# MGC3130.net
KiCad netlist of a schematic drawn in Altium Designer
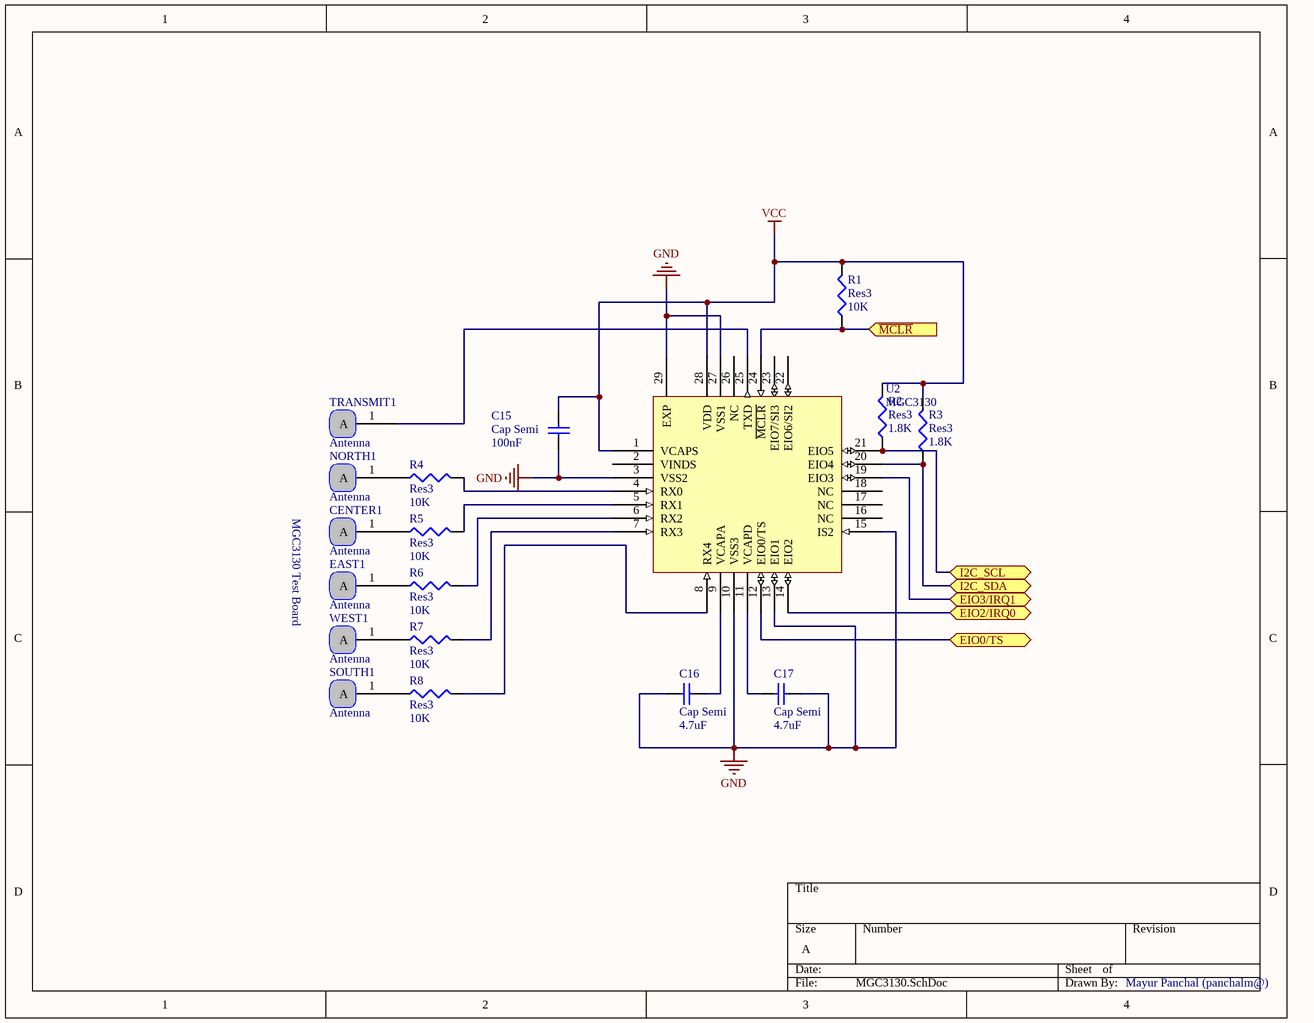
[diagram p0: MGC3130.SchDoc]

(export (version "E")
  (design (tool "Eeschema 10.0.6"))
  (components
    (comp (ref "C15")
      (value "Cap Semi")
      (footprint "1608[0603]")
      (description "Capacitor (Semiconductor SIM Model)")
      (fields (field (name "ALTIUM_VALUE") "100nF") (field (name "PUBLISHER") "Altium Limited"))
      (libsource (lib "Miscellaneous Devices") (part "Cap Semi"))
    )
    (comp (ref "C16")
      (value "Cap Semi")
      (footprint "1608[0603]")
      (description "Capacitor (Semiconductor SIM Model)")
      (fields (field (name "ALTIUM_VALUE") "4.7uF") (field (name "PUBLISHER") "Altium Limited"))
      (libsource (lib "Miscellaneous Devices") (part "Cap Semi"))
    )
    (comp (ref "C17")
      (value "Cap Semi")
      (footprint "1608[0603]")
      (description "Capacitor (Semiconductor SIM Model)")
      (fields (field (name "ALTIUM_VALUE") "4.7uF") (field (name "PUBLISHER") "Altium Limited"))
      (libsource (lib "Miscellaneous Devices") (part "Cap Semi"))
    )
    (comp (ref "CENTER1") (value "Antenna") (libsource (lib "Custom Parts") (part "Center Antenna")))
    (comp (ref "EAST1")
      (value "Antenna")
      (footprint "Vertical Electrode")
      (libsource (lib "Custom Parts") (part "East Antenna"))
    )
    (comp (ref "NORTH1")
      (value "Antenna")
      (footprint "Horizontal Electrode")
      (libsource (lib "Custom Parts") (part "North Antenna"))
    )
    (comp (ref "R1")
      (value "Res3")
      (footprint "J1-0603")
      (description "Resistor")
      (fields (field (name "ALTIUM_VALUE") "10K") (field (name "PUBLISHER") "Altium Limited"))
      (libsource (lib "Miscellaneous Devices") (part "Res3"))
    )
    (comp (ref "R2")
      (value "Res3")
      (footprint "J1-0603")
      (description "Resistor")
      (fields (field (name "ALTIUM_VALUE") "1.8K") (field (name "PUBLISHER") "Altium Limited"))
      (libsource (lib "Miscellaneous Devices") (part "Res3"))
    )
    (comp (ref "R3")
      (value "Res3")
      (footprint "J1-0603")
      (description "Resistor")
      (fields (field (name "ALTIUM_VALUE") "1.8K") (field (name "PUBLISHER") "Altium Limited"))
      (libsource (lib "Miscellaneous Devices") (part "Res3"))
    )
    (comp (ref "R4")
      (value "Res3")
      (footprint "J1-0603")
      (description "Resistor")
      (fields (field (name "ALTIUM_VALUE") "10K") (field (name "PUBLISHER") "Altium Limited"))
      (libsource (lib "Miscellaneous Devices") (part "Res3"))
    )
    (comp (ref "R5")
      (value "Res3")
      (footprint "J1-0603")
      (description "Resistor")
      (fields (field (name "ALTIUM_VALUE") "10K") (field (name "PUBLISHER") "Altium Limited"))
      (libsource (lib "Miscellaneous Devices") (part "Res3"))
    )
    (comp (ref "R6")
      (value "Res3")
      (footprint "J1-0603")
      (description "Resistor")
      (fields (field (name "ALTIUM_VALUE") "10K") (field (name "PUBLISHER") "Altium Limited"))
      (libsource (lib "Miscellaneous Devices") (part "Res3"))
    )
    (comp (ref "R7")
      (value "Res3")
      (footprint "J1-0603")
      (description "Resistor")
      (fields (field (name "ALTIUM_VALUE") "10K") (field (name "PUBLISHER") "Altium Limited"))
      (libsource (lib "Miscellaneous Devices") (part "Res3"))
    )
    (comp (ref "R8")
      (value "Res3")
      (footprint "J1-0603")
      (description "Resistor")
      (fields (field (name "ALTIUM_VALUE") "10K") (field (name "PUBLISHER") "Altium Limited"))
      (libsource (lib "Miscellaneous Devices") (part "Res3"))
    )
    (comp (ref "SOUTH1")
      (value "Antenna")
      (footprint "Horizontal Electrode")
      (libsource (lib "Custom Parts") (part "South Antenna"))
    )
    (comp (ref "TRANSMIT1") (value "Antenna") (libsource (lib "Custom Parts") (part "Transmit Antenna")))
    (comp (ref "U2")
      (value "MGC3130")
      (footprint "QFN28")
      (description "Gesture Recognition IC")
      (libsource (lib "Custom Parts") (part "MGC3130"))
    )
    (comp (ref "WEST1")
      (value "Antenna")
      (footprint "Vertical Electrode")
      (libsource (lib "Custom Parts") (part "West Antenna"))
    )
  )
  (nets
    (net (code "1") (name "/EIO0{slash}TS") (class "Default")
      (node (ref "U2") (pin "12") (pinfunction "EIO0/TS_12") (pintype "bidirectional"))
    )
    (net (code "2") (name "/EIO2{slash}IRQ0") (class "Default")
      (node (ref "U2") (pin "14") (pinfunction "EIO2_14") (pintype "bidirectional"))
    )
    (net (code "3") (name "/EIO3{slash}IRQ1") (class "Default")
      (node (ref "U2") (pin "19") (pinfunction "EIO3_19") (pintype "bidirectional"))
    )
    (net (code "4") (name "/I2C_SCL") (class "Default")
      (node (ref "R2") (pin "1") (pinfunction "1_1") (pintype "passive"))
      (node (ref "U2") (pin "21") (pinfunction "EIO5_21") (pintype "bidirectional"))
    )
    (net (code "5") (name "/I2C_SDA") (class "Default")
      (node (ref "R3") (pin "1") (pinfunction "1_1") (pintype "passive"))
      (node (ref "U2") (pin "20") (pinfunction "EIO4_20") (pintype "bidirectional"))
    )
    (net (code "6") (name "/~{MCLR}") (class "Default")
      (node (ref "R1") (pin "1") (pinfunction "1_1") (pintype "passive"))
      (node (ref "U2") (pin "24") (pinfunction "~{MCLR}_24") (pintype "input"))
    )
    (net (code "7") (name "GND") (class "Default")
      (node (ref "C15") (pin "1") (pinfunction "1_1") (pintype "passive"))
      (node (ref "C16") (pin "1") (pinfunction "1_1") (pintype "passive"))
      (node (ref "C17") (pin "2") (pinfunction "2_2") (pintype "passive"))
      (node (ref "U2") (pin "10") (pinfunction "VSS3_10") (pintype "power_in"))
      (node (ref "U2") (pin "13") (pinfunction "EIO1_13") (pintype "bidirectional"))
      (node (ref "U2") (pin "15") (pinfunction "IS2_15") (pintype "input"))
      (node (ref "U2") (pin "27") (pinfunction "VSS1_27") (pintype "power_in"))
      (node (ref "U2") (pin "29") (pinfunction "EXP_29") (pintype "power_in"))
      (node (ref "U2") (pin "3") (pinfunction "VSS2_3") (pintype "power_in"))
    )
    (net (code "8") (name "Net-(CENTER1-A)") (class "Default")
      (node (ref "CENTER1") (pin "1") (pinfunction "A_1") (pintype "passive"))
      (node (ref "R5") (pin "1") (pinfunction "1_1") (pintype "passive"))
    )
    (net (code "9") (name "Net-(EAST1-A)") (class "Default")
      (node (ref "EAST1") (pin "1") (pinfunction "A_1") (pintype "passive"))
      (node (ref "R6") (pin "1") (pinfunction "1_1") (pintype "passive"))
    )
    (net (code "10") (name "Net-(NORTH1-A)") (class "Default")
      (node (ref "NORTH1") (pin "1") (pinfunction "A_1") (pintype "passive"))
      (node (ref "R4") (pin "1") (pinfunction "1_1") (pintype "passive"))
    )
    (net (code "11") (name "Net-(SOUTH1-A)") (class "Default")
      (node (ref "R8") (pin "1") (pinfunction "1_1") (pintype "passive"))
      (node (ref "SOUTH1") (pin "1") (pinfunction "A_1") (pintype "passive"))
    )
    (net (code "12") (name "Net-(TRANSMIT1-A)") (class "Default")
      (node (ref "TRANSMIT1") (pin "1") (pinfunction "A_1") (pintype "passive"))
      (node (ref "U2") (pin "25") (pinfunction "TXD_25") (pintype "output"))
    )
    (net (code "13") (name "Net-(U2-RX0)") (class "Default")
      (node (ref "R4") (pin "2") (pinfunction "2_2") (pintype "passive"))
      (node (ref "U2") (pin "4") (pinfunction "RX0_4") (pintype "input"))
    )
    (net (code "14") (name "Net-(U2-RX1)") (class "Default")
      (node (ref "R5") (pin "2") (pinfunction "2_2") (pintype "passive"))
      (node (ref "U2") (pin "5") (pinfunction "RX1_5") (pintype "input"))
    )
    (net (code "15") (name "Net-(U2-RX2)") (class "Default")
      (node (ref "R6") (pin "2") (pinfunction "2_2") (pintype "passive"))
      (node (ref "U2") (pin "6") (pinfunction "RX2_6") (pintype "input"))
    )
    (net (code "16") (name "Net-(U2-RX3)") (class "Default")
      (node (ref "R7") (pin "2") (pinfunction "2_2") (pintype "passive"))
      (node (ref "U2") (pin "7") (pinfunction "RX3_7") (pintype "input"))
    )
    (net (code "17") (name "Net-(U2-RX4)") (class "Default")
      (node (ref "R8") (pin "2") (pinfunction "2_2") (pintype "passive"))
      (node (ref "U2") (pin "8") (pinfunction "RX4_8") (pintype "input"))
    )
    (net (code "18") (name "Net-(U2-VCAPA)") (class "Default")
      (node (ref "C16") (pin "2") (pinfunction "2_2") (pintype "passive"))
      (node (ref "U2") (pin "9") (pinfunction "VCAPA_9") (pintype "power_in"))
    )
    (net (code "19") (name "Net-(U2-VCAPD)") (class "Default")
      (node (ref "C17") (pin "1") (pinfunction "1_1") (pintype "passive"))
      (node (ref "U2") (pin "11") (pinfunction "VCAPD_11") (pintype "power_in"))
    )
    (net (code "20") (name "Net-(WEST1-A)") (class "Default")
      (node (ref "R7") (pin "1") (pinfunction "1_1") (pintype "passive"))
      (node (ref "WEST1") (pin "1") (pinfunction "A_1") (pintype "passive"))
    )
    (net (code "21") (name "VCC") (class "Default")
      (node (ref "C15") (pin "2") (pinfunction "2_2") (pintype "passive"))
      (node (ref "R1") (pin "2") (pinfunction "2_2") (pintype "passive"))
      (node (ref "R2") (pin "2") (pinfunction "2_2") (pintype "passive"))
      (node (ref "R3") (pin "2") (pinfunction "2_2") (pintype "passive"))
      (node (ref "U2") (pin "1") (pinfunction "VCAPS_1") (pintype "power_in"))
      (node (ref "U2") (pin "28") (pinfunction "VDD_28") (pintype "power_in"))
    )
    (net (code "22") (name "unconnected-(U2-EIO6{slash}SI2-Pad22)") (class "Default")
      (node (ref "U2") (pin "22") (pinfunction "EIO6/SI2_22") (pintype "bidirectional"))
    )
    (net (code "23") (name "unconnected-(U2-EIO7{slash}SI3-Pad23)") (class "Default")
      (node (ref "U2") (pin "23") (pinfunction "EIO7/SI3_23") (pintype "bidirectional"))
    )
    (net (code "24") (name "unconnected-(U2-NC-Pad16)") (class "Default")
      (node (ref "U2") (pin "16") (pinfunction "NC_16") (pintype "passive"))
    )
    (net (code "25") (name "unconnected-(U2-NC-Pad17)") (class "Default")
      (node (ref "U2") (pin "17") (pinfunction "NC_17") (pintype "passive"))
    )
    (net (code "26") (name "unconnected-(U2-NC-Pad18)") (class "Default")
      (node (ref "U2") (pin "18") (pinfunction "NC_18") (pintype "passive"))
    )
    (net (code "27") (name "unconnected-(U2-NC-Pad26)") (class "Default")
      (node (ref "U2") (pin "26") (pinfunction "NC_26") (pintype "passive"))
    )
    (net (code "28") (name "unconnected-(U2-VINDS-Pad2)") (class "Default")
      (node (ref "U2") (pin "2") (pinfunction "VINDS_2") (pintype "power_in"))
    )
  )
)
